# Microchip.net
KiCad netlist of a schematic drawn in Altium Designer
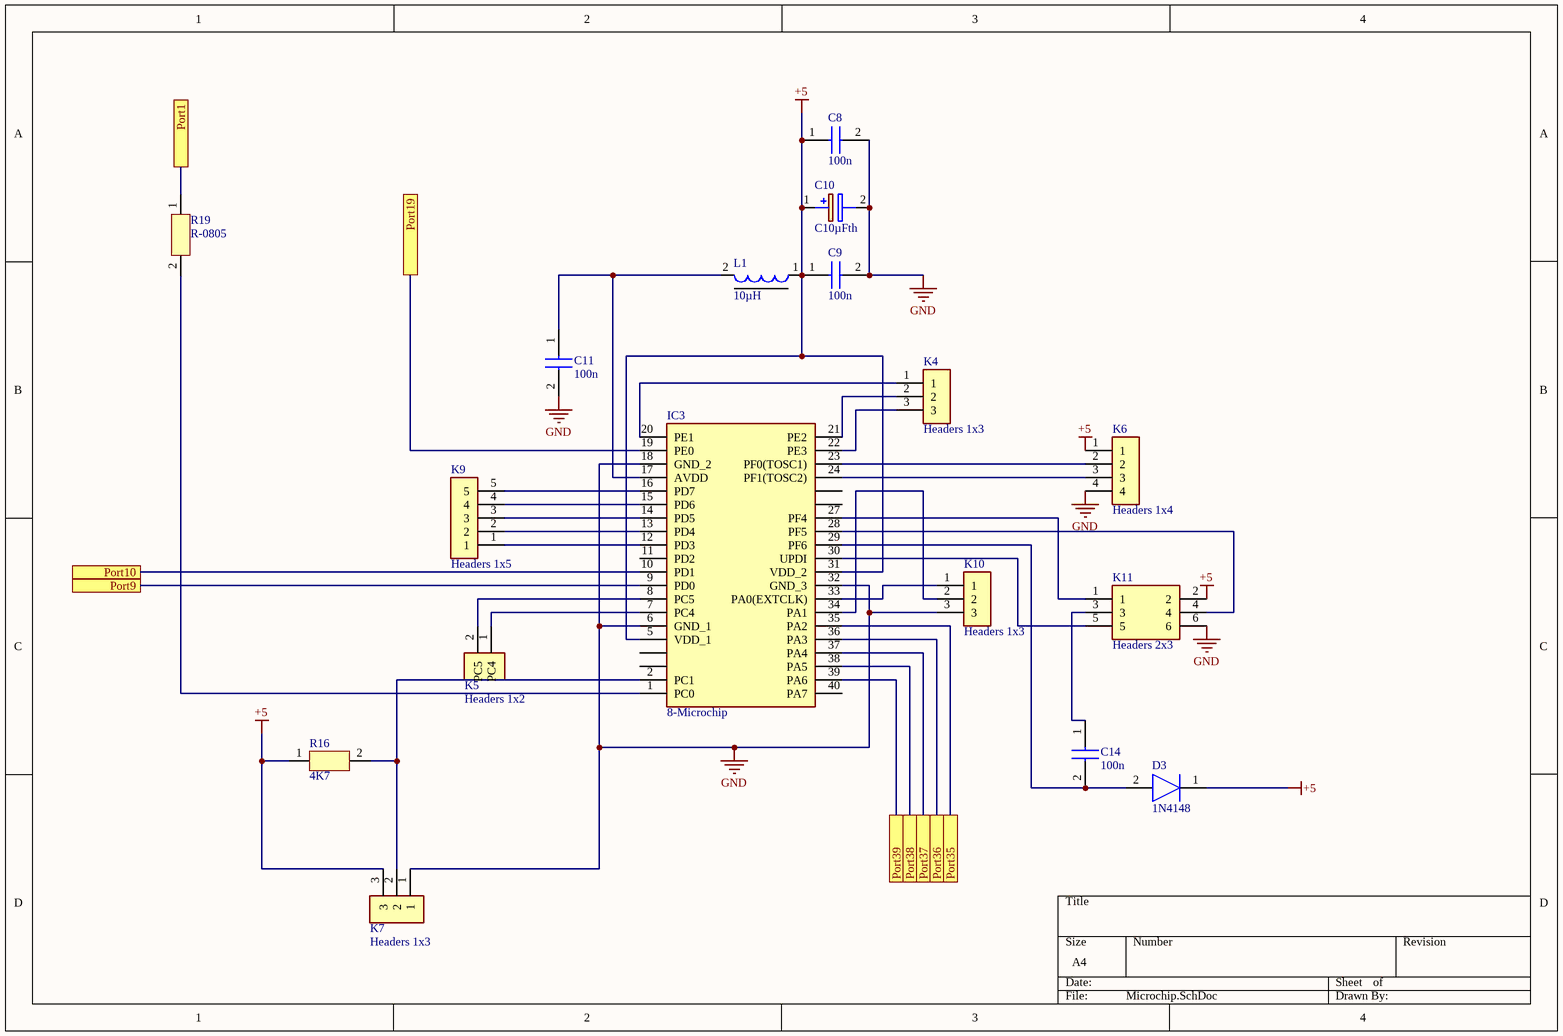
[diagram p0: Microchip.SchDoc]

(export (version "E")
  (design (tool "Eeschema 10.0.6"))
  (components
    (comp (ref "C8")
      (value "100n")
      (footprint "0805")
      (description "Capacitor")
      (fields (field (name "MANUFACTURER_PART_NUMBER") "C0805C301G5GACTU"))
      (libsource (lib "Soldeerbout_12002498") (part "C0805smd"))
    )
    (comp (ref "C9")
      (value "100n")
      (footprint "0805")
      (description "Capacitor")
      (fields (field (name "MANUFACTURER_PART_NUMBER") "C0805C301G5GACTU"))
      (libsource (lib "Soldeerbout_12002498") (part "C0805smd"))
    )
    (comp (ref "C10")
      (value "C10µFth")
      (footprint "C10µFth")
      (description "Capacitor Polarised")
      (fields
        (field (name "MOUSER2 PART NUMBER") "667-ECA-1HM100I")
        (field (name "MANUFACTURER_PART_NUMBER") "ECA-1HM100I")
      )
      (libsource (lib "Soldeerbout_12002498") (part "C10µFth"))
    )
    (comp (ref "C11")
      (value "100n")
      (footprint "0805")
      (description "Capacitor")
      (fields (field (name "MANUFACTURER_PART_NUMBER") "C0805C301G5GACTU"))
      (libsource (lib "Soldeerbout_12002498") (part "C0805smd"))
    )
    (comp (ref "C14")
      (value "100n")
      (footprint "0805")
      (description "Capacitor")
      (fields (field (name "MANUFACTURER_PART_NUMBER") "C0805C301G5GACTU"))
      (libsource (lib "Soldeerbout_12002498") (part "C0805smd"))
    )
    (comp (ref "D3")
      (value "1N4148")
      (footprint "1N4148")
      (description "Diode")
      (libsource (lib "Soldeerbout_12002498") (part "1N4148"))
    )
    (comp (ref "IC3")
      (value "8-Microchip")
      (footprint "8-bit-MCU-ATMEGA4809-PF")
      (description "Integrated Circuit")
      (fields
        (field (name "MOUSER2 PART NUMBER") "556-ATMEGA4809-PF")
        (field (name "MANUFACTURER_PART_NUMBER") "ATMEGA4809-PF")
      )
      (libsource (lib "Soldeerbout_12002498") (part "8-Microchip"))
    )
    (comp (ref "K4")
      (value "Headers 1x3")
      (footprint "Headers 1x3")
      (description "Connector")
      (fields (field (name "MANUFACTURER_PART_NUMBER") "2-826646-0"))
      (libsource (lib "") (part "Headers 1x3_1"))
    )
    (comp (ref "K5")
      (value "Headers 1x2")
      (footprint "Headers 1x2")
      (description "Connector")
      (fields (field (name "MANUFACTURER_PART_NUMBER") "2-826646-0"))
      (libsource (lib "Soldeerbout_12002498") (part "Headers 1x2"))
    )
    (comp (ref "K6")
      (value "Headers 1x4")
      (footprint "Headers 1x4")
      (description "Connector")
      (fields (field (name "MANUFACTURER_PART_NUMBER") "2-826646-0"))
      (libsource (lib "Soldeerbout_12002498") (part "Headers 1x4"))
    )
    (comp (ref "K7")
      (value "Headers 1x3")
      (footprint "Headers 1x3")
      (description "Connector")
      (fields (field (name "MANUFACTURER_PART_NUMBER") "2-826646-0"))
      (libsource (lib "Soldeerbout_12002498") (part "Headers 1x3"))
    )
    (comp (ref "K9")
      (value "Headers 1x5")
      (footprint "Headers 1x5")
      (description "Connector")
      (fields (field (name "MANUFACTURER_PART_NUMBER") "2-826646-0"))
      (libsource (lib "Soldeerbout_12002498") (part "Headers 1x5"))
    )
    (comp (ref "K10")
      (value "Headers 1x3")
      (footprint "Headers 1x3")
      (description "Connector")
      (fields (field (name "MANUFACTURER_PART_NUMBER") "2-826646-0"))
      (libsource (lib "") (part "Headers 1x3_1"))
    )
    (comp (ref "K11")
      (value "Headers 2x3")
      (footprint "Headers 2x3")
      (description "Connector")
      (fields
        (field (name "MOUSER2 PART NUMBER") "855-M20-9761042")
        (field (name "MANUFACTURER_PART_NUMBER") "M20-9761042")
      )
      (libsource (lib "Soldeerbout_12002498") (part "Headers 2x3"))
    )
    (comp (ref "L1")
      (value "10µH")
      (footprint "Soldeerbout_12002498:Smoorspoel-130mA")
      (description "THT Common Mode Power Line Choke WE-CMB, L = 1.00 mH")
      (libsource (lib "Soldeerbout_12002498") (part "Smoorspoel-130mA"))
    )
    (comp (ref "R16")
      (value "4K7")
      (footprint "0805")
      (description "Resistor")
      (fields (field (name "MANUFACTURER_PART_NUMBER") "TNPU0805500RAZEN00"))
      (libsource (lib "Soldeerbout_12002498") (part "R-0805"))
    )
    (comp (ref "R19")
      (value "R-0805")
      (footprint "0805")
      (description "Resistor")
      (fields (field (name "MANUFACTURER_PART_NUMBER") "TNPU0805500RAZEN00"))
      (libsource (lib "") (part "R-0805_1"))
    )
  )
  (nets
    (net (code "1") (name "+5") (class "Default")
      (node (ref "C10") (pin "1") (pinfunction "+_1") (pintype "passive"))
      (node (ref "C8") (pin "1") (pinfunction "1_1") (pintype "passive"))
      (node (ref "C9") (pin "1") (pinfunction "1_1") (pintype "passive"))
      (node (ref "D3") (pin "1") (pinfunction "K_1") (pintype "passive"))
      (node (ref "IC3") (pin "31") (pinfunction "VDD_2_31") (pintype "passive"))
      (node (ref "IC3") (pin "5") (pinfunction "VDD_1_5") (pintype "passive"))
      (node (ref "K11") (pin "2") (pinfunction "2_2") (pintype "passive"))
      (node (ref "K6") (pin "1") (pinfunction "1_1") (pintype "passive"))
      (node (ref "K7") (pin "3") (pinfunction "3_3") (pintype "passive"))
      (node (ref "L1") (pin "1") (pinfunction "4_1") (pintype "passive"))
      (node (ref "R16") (pin "1") (pinfunction "1_1") (pintype "passive"))
    )
    (net (code "2") (name "/Port1") (class "Default")
      (node (ref "R19") (pin "1") (pinfunction "1_1") (pintype "passive"))
    )
    (net (code "3") (name "/Port9") (class "Default")
      (node (ref "IC3") (pin "9") (pinfunction "PD0_9") (pintype "passive"))
    )
    (net (code "4") (name "/Port10") (class "Default")
      (node (ref "IC3") (pin "10") (pinfunction "PD1_10") (pintype "passive"))
    )
    (net (code "5") (name "/Port19") (class "Default")
      (node (ref "IC3") (pin "19") (pinfunction "PE0_19") (pintype "passive"))
    )
    (net (code "6") (name "/Port35") (class "Default")
      (node (ref "IC3") (pin "35") (pinfunction "PA2_35") (pintype "passive"))
    )
    (net (code "7") (name "/Port36") (class "Default")
      (node (ref "IC3") (pin "36") (pinfunction "PA3_36") (pintype "passive"))
    )
    (net (code "8") (name "/Port37") (class "Default")
      (node (ref "IC3") (pin "37") (pinfunction "PA4_37") (pintype "passive"))
    )
    (net (code "9") (name "/Port38") (class "Default")
      (node (ref "IC3") (pin "38") (pinfunction "PA5_38") (pintype "passive"))
    )
    (net (code "10") (name "/Port39") (class "Default")
      (node (ref "IC3") (pin "39") (pinfunction "PA6_39") (pintype "passive"))
    )
    (net (code "11") (name "GND") (class "Default")
      (node (ref "C10") (pin "2") (pinfunction "-_2") (pintype "passive"))
      (node (ref "C11") (pin "2") (pinfunction "2_2") (pintype "passive"))
      (node (ref "C8") (pin "2") (pinfunction "2_2") (pintype "passive"))
      (node (ref "C9") (pin "2") (pinfunction "2_2") (pintype "passive"))
      (node (ref "IC3") (pin "18") (pinfunction "GND_2_18") (pintype "passive"))
      (node (ref "IC3") (pin "32") (pinfunction "GND_3_32") (pintype "passive"))
      (node (ref "IC3") (pin "6") (pinfunction "GND_1_6") (pintype "passive"))
      (node (ref "K10") (pin "3") (pinfunction "3_3") (pintype "passive"))
      (node (ref "K11") (pin "6") (pinfunction "6_6") (pintype "passive"))
      (node (ref "K6") (pin "4") (pinfunction "4_4") (pintype "passive"))
      (node (ref "K7") (pin "1") (pinfunction "1_1") (pintype "passive"))
    )
    (net (code "12") (name "Net-(C14-Pad1)") (class "Default")
      (node (ref "C14") (pin "1") (pinfunction "1_1") (pintype "passive"))
      (node (ref "K11") (pin "3") (pinfunction "3_3") (pintype "passive"))
    )
    (net (code "13") (name "Net-(D3-A)") (class "Default")
      (node (ref "C14") (pin "2") (pinfunction "2_2") (pintype "passive"))
      (node (ref "D3") (pin "2") (pinfunction "A_2") (pintype "passive"))
      (node (ref "IC3") (pin "29") (pinfunction "PF6_29") (pintype "passive"))
    )
    (net (code "14") (name "Net-(IC3-AVDD)") (class "Default")
      (node (ref "C11") (pin "1") (pinfunction "1_1") (pintype "passive"))
      (node (ref "IC3") (pin "17") (pinfunction "AVDD_17") (pintype "passive"))
      (node (ref "L1") (pin "2") (pinfunction "7_2") (pintype "passive"))
    )
    (net (code "15") (name "Net-(IC3-PA0(EXTCLK))") (class "Default")
      (node (ref "IC3") (pin "33") (pinfunction "PA0(EXTCLK)_33") (pintype "passive"))
      (node (ref "K10") (pin "1") (pinfunction "1_1") (pintype "passive"))
    )
    (net (code "16") (name "Net-(IC3-PA1)") (class "Default")
      (node (ref "IC3") (pin "34") (pinfunction "PA1_34") (pintype "passive"))
      (node (ref "K10") (pin "2") (pinfunction "2_2") (pintype "passive"))
    )
    (net (code "17") (name "Net-(IC3-PC0)") (class "Default")
      (node (ref "IC3") (pin "1") (pinfunction "PC0_1") (pintype "passive"))
      (node (ref "R19") (pin "2") (pinfunction "2_2") (pintype "passive"))
    )
    (net (code "18") (name "Net-(IC3-PC1)") (class "Default")
      (node (ref "IC3") (pin "2") (pinfunction "PC1_2") (pintype "passive"))
      (node (ref "K7") (pin "2") (pinfunction "2_2") (pintype "passive"))
      (node (ref "R16") (pin "2") (pinfunction "2_2") (pintype "passive"))
    )
    (net (code "19") (name "Net-(IC3-PC4)") (class "Default")
      (node (ref "IC3") (pin "7") (pinfunction "PC4_7") (pintype "passive"))
      (node (ref "K5") (pin "1") (pinfunction "PC4_1") (pintype "passive"))
    )
    (net (code "20") (name "Net-(IC3-PC5)") (class "Default")
      (node (ref "IC3") (pin "8") (pinfunction "PC5_8") (pintype "passive"))
      (node (ref "K5") (pin "2") (pinfunction "PC5_2") (pintype "passive"))
    )
    (net (code "21") (name "Net-(IC3-PD3)") (class "Default")
      (node (ref "IC3") (pin "12") (pinfunction "PD3_12") (pintype "passive"))
      (node (ref "K9") (pin "1") (pinfunction "1_1") (pintype "passive"))
    )
    (net (code "22") (name "Net-(IC3-PD4)") (class "Default")
      (node (ref "IC3") (pin "13") (pinfunction "PD4_13") (pintype "passive"))
      (node (ref "K9") (pin "2") (pinfunction "2_2") (pintype "passive"))
    )
    (net (code "23") (name "Net-(IC3-PD5)") (class "Default")
      (node (ref "IC3") (pin "14") (pinfunction "PD5_14") (pintype "passive"))
      (node (ref "K9") (pin "3") (pinfunction "3_3") (pintype "passive"))
    )
    (net (code "24") (name "Net-(IC3-PD6)") (class "Default")
      (node (ref "IC3") (pin "15") (pinfunction "PD6_15") (pintype "passive"))
      (node (ref "K9") (pin "4") (pinfunction "4_4") (pintype "passive"))
    )
    (net (code "25") (name "Net-(IC3-PD7)") (class "Default")
      (node (ref "IC3") (pin "16") (pinfunction "PD7_16") (pintype "passive"))
      (node (ref "K9") (pin "5") (pinfunction "5_5") (pintype "passive"))
    )
    (net (code "26") (name "Net-(IC3-PE1)") (class "Default")
      (node (ref "IC3") (pin "20") (pinfunction "PE1_20") (pintype "passive"))
      (node (ref "K4") (pin "1") (pinfunction "1_1") (pintype "passive"))
    )
    (net (code "27") (name "Net-(IC3-PE2)") (class "Default")
      (node (ref "IC3") (pin "21") (pinfunction "PE2_21") (pintype "passive"))
      (node (ref "K4") (pin "2") (pinfunction "2_2") (pintype "passive"))
    )
    (net (code "28") (name "Net-(IC3-PE3)") (class "Default")
      (node (ref "IC3") (pin "22") (pinfunction "PE3_22") (pintype "passive"))
      (node (ref "K4") (pin "3") (pinfunction "3_3") (pintype "passive"))
    )
    (net (code "29") (name "Net-(IC3-PF0(TOSC1))") (class "Default")
      (node (ref "IC3") (pin "23") (pinfunction "PF0(TOSC1)_23") (pintype "passive"))
      (node (ref "K6") (pin "2") (pinfunction "2_2") (pintype "passive"))
    )
    (net (code "30") (name "Net-(IC3-PF1(TOSC2))") (class "Default")
      (node (ref "IC3") (pin "24") (pinfunction "PF1(TOSC2)_24") (pintype "passive"))
      (node (ref "K6") (pin "3") (pinfunction "3_3") (pintype "passive"))
    )
    (net (code "31") (name "Net-(IC3-PF4)") (class "Default")
      (node (ref "IC3") (pin "27") (pinfunction "PF4_27") (pintype "passive"))
      (node (ref "K11") (pin "1") (pinfunction "1_1") (pintype "passive"))
    )
    (net (code "32") (name "Net-(IC3-PF5)") (class "Default")
      (node (ref "IC3") (pin "28") (pinfunction "PF5_28") (pintype "passive"))
      (node (ref "K11") (pin "4") (pinfunction "4_4") (pintype "passive"))
    )
    (net (code "33") (name "Net-(IC3-UPDI)") (class "Default")
      (node (ref "IC3") (pin "30") (pinfunction "UPDI_30") (pintype "passive"))
      (node (ref "K11") (pin "5") (pinfunction "5_5") (pintype "passive"))
    )
    (net (code "34") (name "unconnected-(IC3-PA7-Pad40)") (class "Default")
      (node (ref "IC3") (pin "40") (pinfunction "PA7_40") (pintype "passive"))
    )
    (net (code "35") (name "unconnected-(IC3-PC2-Pad3)") (class "Default")
      (node (ref "IC3") (pin "3") (pinfunction "PC2_3") (pintype "passive"))
    )
    (net (code "36") (name "unconnected-(IC3-PC3-Pad4)") (class "Default")
      (node (ref "IC3") (pin "4") (pinfunction "PC3_4") (pintype "passive"))
    )
    (net (code "37") (name "unconnected-(IC3-PD2-Pad11)") (class "Default")
      (node (ref "IC3") (pin "11") (pinfunction "PD2_11") (pintype "passive"))
    )
    (net (code "38") (name "unconnected-(IC3-PF2-Pad25)") (class "Default")
      (node (ref "IC3") (pin "25") (pinfunction "PF2_25") (pintype "passive"))
    )
    (net (code "39") (name "unconnected-(IC3-PF3-Pad26)") (class "Default")
      (node (ref "IC3") (pin "26") (pinfunction "PF3_26") (pintype "passive"))
    )
  )
)
